# bistable.net
KiCad netlist of a schematic drawn in EAGLE
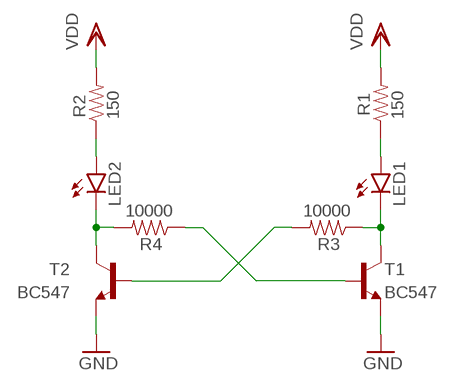
[diagram p0: schematic, sheet 1]

(export (version "E")
  (design (tool "Eeschema 10.0.6"))
  (components
    (comp (ref "LED1")
      (value "LED5MM")
      (footprint "eagle-import:LED5MM")
      (libsource (lib "eagle-import") (part "LED5MM"))
    )
    (comp (ref "LED2")
      (value "LED5MM")
      (footprint "eagle-import:LED5MM")
      (libsource (lib "eagle-import") (part "LED5MM"))
    )
    (comp (ref "R1")
      (value "150")
      (footprint "eagle-import:AXIAL-0.5")
      (libsource (lib "eagle-import") (part "RESISTORPTH-1/2W"))
    )
    (comp (ref "R2")
      (value "150")
      (footprint "eagle-import:AXIAL-0.5")
      (libsource (lib "eagle-import") (part "RESISTORPTH-1/2W"))
    )
    (comp (ref "R3")
      (value "10000")
      (footprint "eagle-import:AXIAL-0.5")
      (libsource (lib "eagle-import") (part "RESISTORPTH-1/2W"))
    )
    (comp (ref "R4")
      (value "10000")
      (footprint "eagle-import:AXIAL-0.5")
      (libsource (lib "eagle-import") (part "RESISTORPTH-1/2W"))
    )
    (comp (ref "T1")
      (value "BC547")
      (footprint "eagle-import:TO92")
      (libsource (lib "eagle-import") (part "BC547"))
    )
    (comp (ref "T2")
      (value "BC547")
      (footprint "eagle-import:TO92")
      (libsource (lib "eagle-import") (part "BC547"))
    )
  )
  (nets
    (net (code "1") (name "GND") (class "Default")
      (node (ref "T1") (pin "1") (pinfunction "E_1") (pintype "passive"))
      (node (ref "T2") (pin "1") (pinfunction "E_1") (pintype "passive"))
    )
    (net (code "2") (name "Net-(LED1-C)") (class "Default")
      (node (ref "LED1") (pin "K") (pinfunction "C_K") (pintype "passive"))
      (node (ref "R3") (pin "P$1") (pinfunction "1_P$1") (pintype "passive"))
      (node (ref "T1") (pin "3") (pinfunction "C_3") (pintype "passive"))
    )
    (net (code "3") (name "Net-(LED2-C)") (class "Default")
      (node (ref "LED2") (pin "K") (pinfunction "C_K") (pintype "passive"))
      (node (ref "R4") (pin "P$2") (pinfunction "2_P$2") (pintype "passive"))
      (node (ref "T2") (pin "3") (pinfunction "C_3") (pintype "passive"))
    )
    (net (code "4") (name "Net-(R1-1)") (class "Default")
      (node (ref "LED1") (pin "A") (pinfunction "A_A") (pintype "passive"))
      (node (ref "R1") (pin "P$1") (pinfunction "1_P$1") (pintype "passive"))
    )
    (net (code "5") (name "Net-(R2-1)") (class "Default")
      (node (ref "LED2") (pin "A") (pinfunction "A_A") (pintype "passive"))
      (node (ref "R2") (pin "P$1") (pinfunction "1_P$1") (pintype "passive"))
    )
    (net (code "6") (name "Net-(R3-2)") (class "Default")
      (node (ref "R3") (pin "P$2") (pinfunction "2_P$2") (pintype "passive"))
      (node (ref "T2") (pin "2") (pinfunction "B_2") (pintype "passive"))
    )
    (net (code "7") (name "Net-(R4-1)") (class "Default")
      (node (ref "R4") (pin "P$1") (pinfunction "1_P$1") (pintype "passive"))
      (node (ref "T1") (pin "2") (pinfunction "B_2") (pintype "passive"))
    )
    (net (code "8") (name "VDD") (class "Default")
      (node (ref "R1") (pin "P$2") (pinfunction "2_P$2") (pintype "passive"))
      (node (ref "R2") (pin "P$2") (pinfunction "2_P$2") (pintype "passive"))
    )
  )
)
